# RGB_Display.net
KiCad netlist of a schematic drawn in Altium Designer
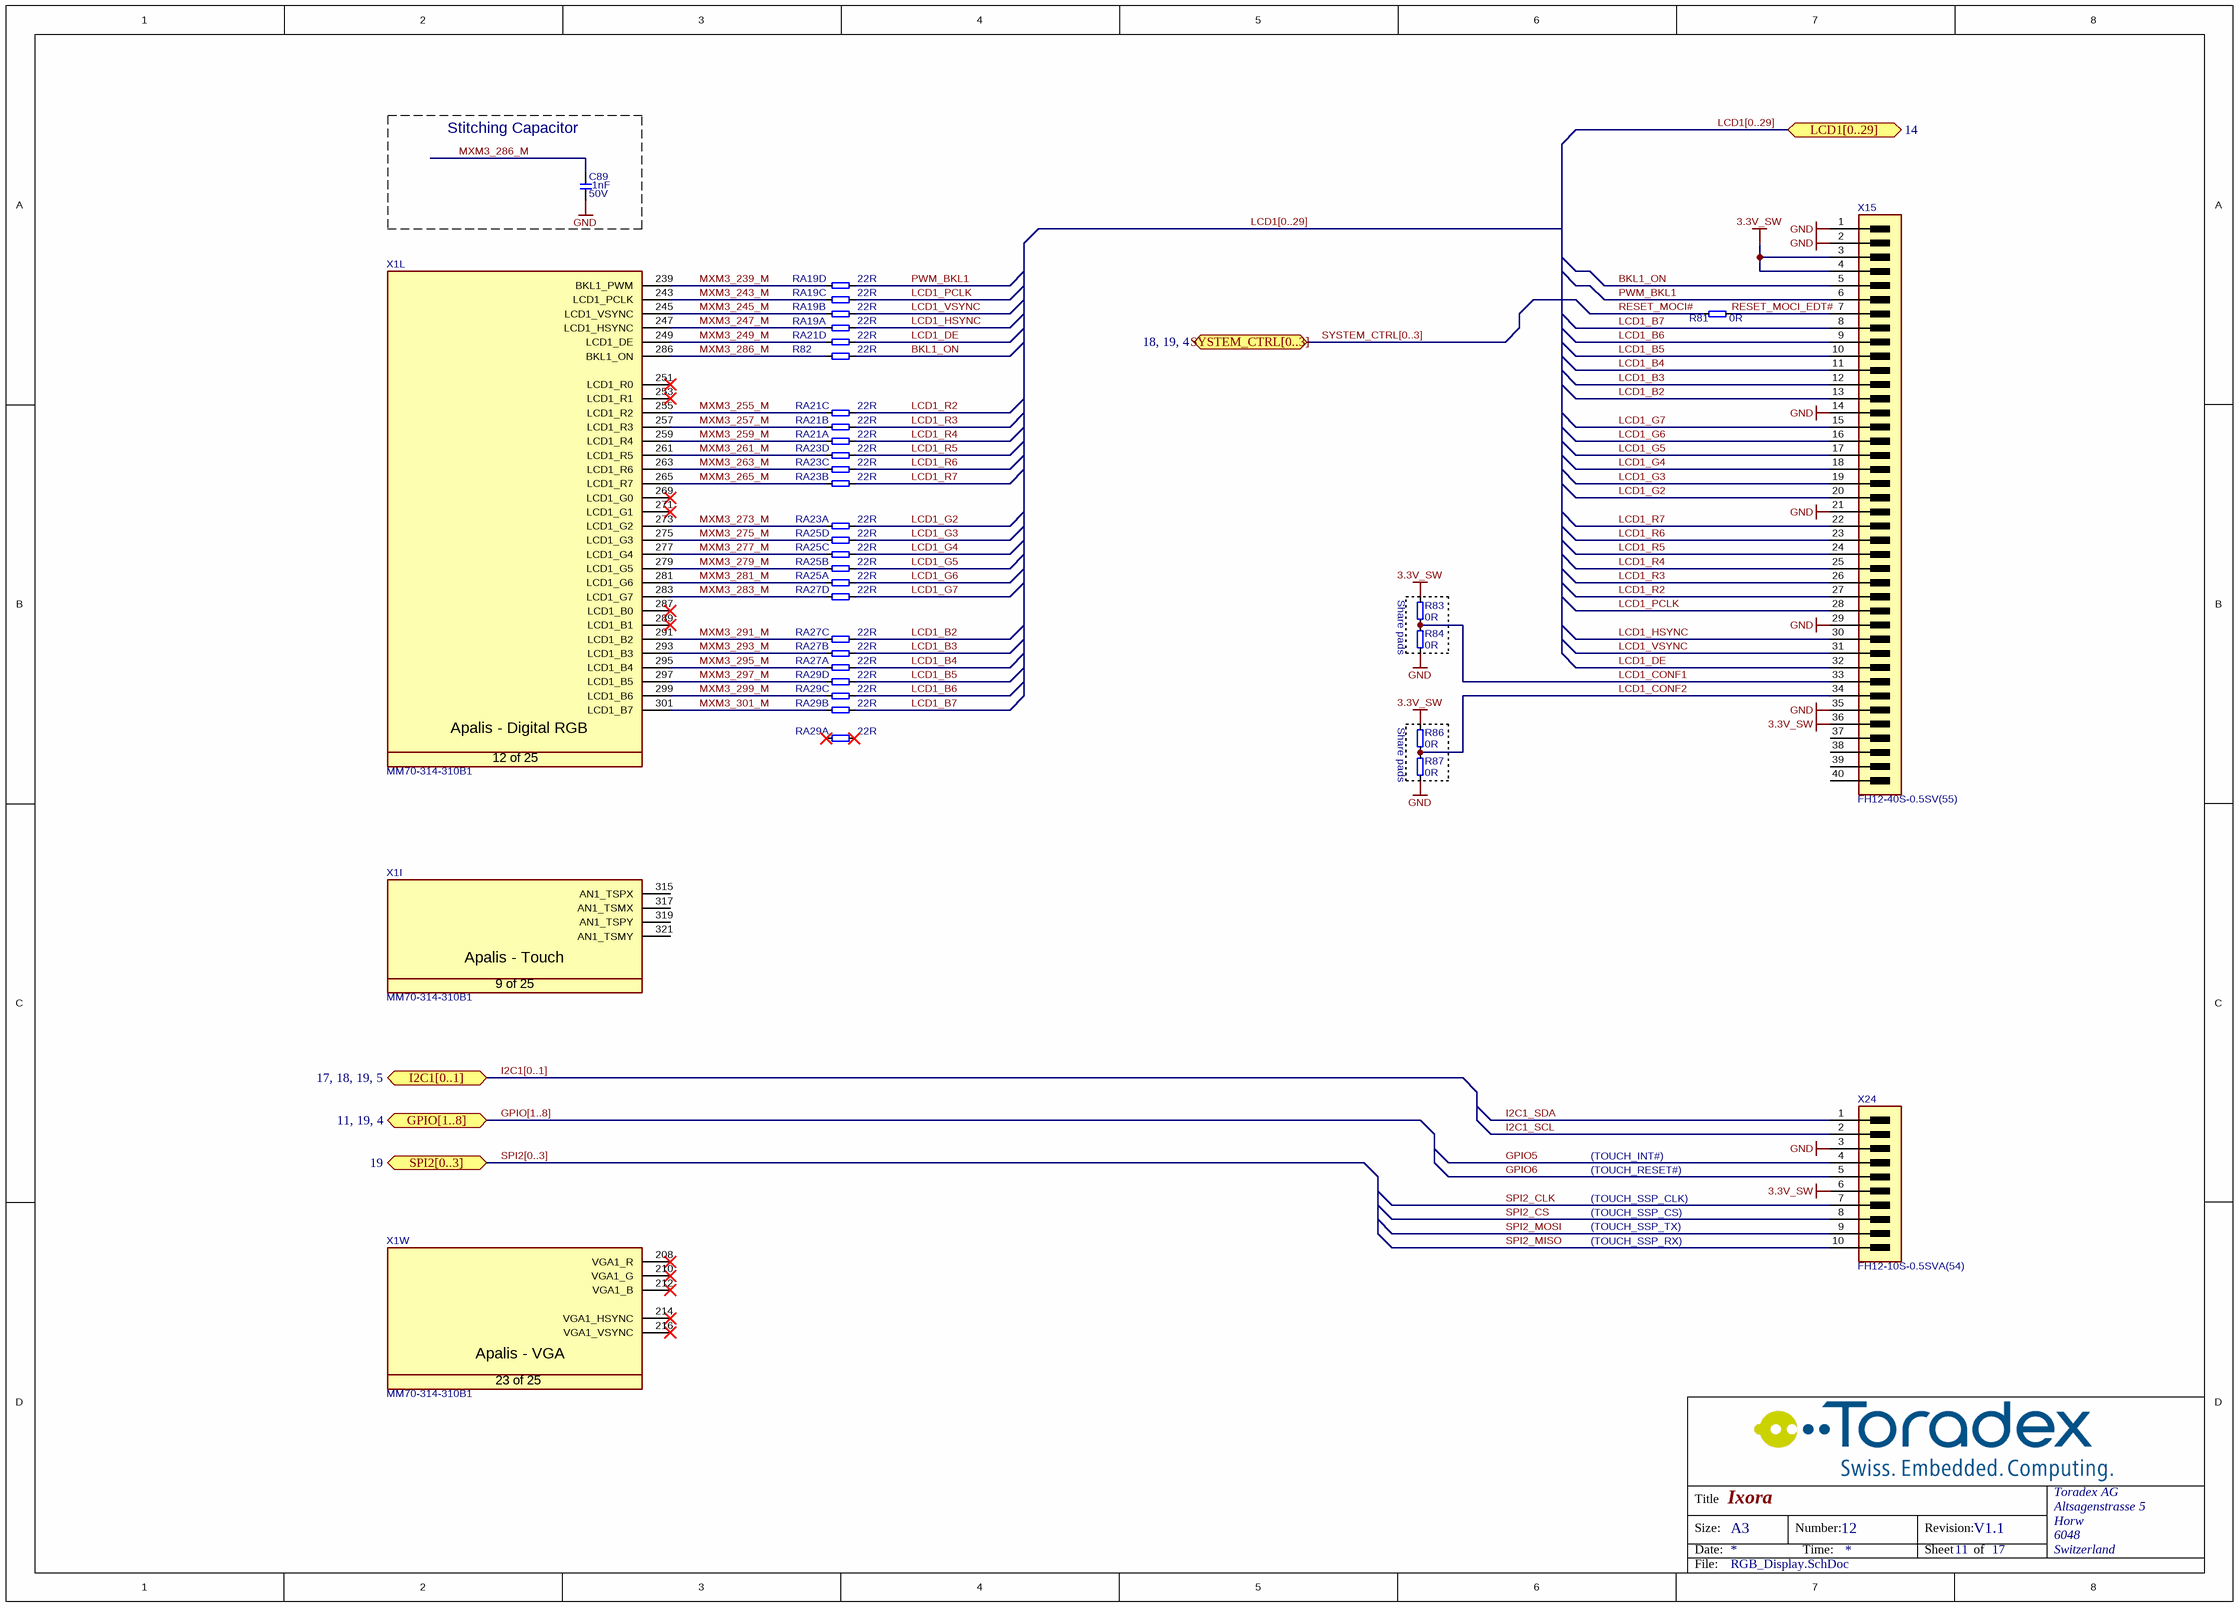
[diagram p0: RGB_Display.SchDoc]

(export (version "E")
  (design (tool "Eeschema 10.0.6"))
  (components
    (comp (ref "C89")
      (value "1nF")
      (footprint "CAPC1005X60N")
      (description "Capacitor Ceramic X7R 1nF 50V 10% 0402")
      (fields (field (name "TOLERANCE") "10%") (field (name "RATING") "50V"))
      (libsource (lib "Ixora") (part "C-X7R-1nF-50V-10%-0402"))
    )
    (comp (ref "R81")
      (value "0R")
      (footprint "RESC1005X40N")
      (description "Resistor 0 ohm 63mW 1% 0402")
      (fields (field (name "TOLERANCE") "1%"))
      (libsource (lib "Ixora") (part "R-0R-63mW-1%-0402"))
    )
    (comp (ref "R82")
      (value "22R")
      (footprint "RESC1005X40N")
      (description "Resistor 22 ohm 63mW 5% 0402")
      (fields (field (name "TOLERANCE") "5%"))
      (libsource (lib "Ixora") (part "R-22R-63mW-5%-0402"))
    )
    (comp (ref "R83")
      (value "0R")
      (footprint "T_RESC0603X30N")
      (description "Resistor 0 ohm 63mW 1% 0603")
      (fields (field (name "TOLERANCE") "1%"))
      (libsource (lib "Ixora") (part "R-0R-63mW-1%-0603"))
    )
    (comp (ref "R84")
      (value "0R")
      (footprint "T_RESC0603X30N")
      (description "Resistor 0 ohm 63mW 1% 0603")
      (fields (field (name "TOLERANCE") "1%"))
      (libsource (lib "Ixora") (part "R-0R-63mW-1%-0603"))
    )
    (comp (ref "R86")
      (value "0R")
      (footprint "T_RESC0603X30N")
      (description "Resistor 0 ohm 63mW 1% 0603")
      (fields (field (name "TOLERANCE") "1%"))
      (libsource (lib "Ixora") (part "R-0R-63mW-1%-0603"))
    )
    (comp (ref "R87")
      (value "0R")
      (footprint "T_RESC0603X30N")
      (description "Resistor 0 ohm 63mW 1% 0603")
      (fields (field (name "TOLERANCE") "1%"))
      (libsource (lib "Ixora") (part "R-0R-63mW-1%-0603"))
    )
    (comp (ref "RA19")
      (value "22R")
      (footprint "T_Resistor_Array_X4")
      (description "Resistor Array 22 R 63mW 5% 1206")
      (fields (field (name "TOLERANCE") "5%"))
      (libsource (lib "Ixora") (part "RA-22R-63mW-5%-1206-div"))
    )
    (comp (ref "RA21")
      (value "22R")
      (footprint "T_Resistor_Array_X4")
      (description "Resistor Array 22 R 63mW 5% 1206")
      (fields (field (name "TOLERANCE") "5%"))
      (libsource (lib "Ixora") (part "RA-22R-63mW-5%-1206-div"))
    )
    (comp (ref "RA23")
      (value "22R")
      (footprint "T_Resistor_Array_X4")
      (description "Resistor Array 22 R 63mW 5% 1206")
      (fields (field (name "TOLERANCE") "5%"))
      (libsource (lib "Ixora") (part "RA-22R-63mW-5%-1206-div"))
    )
    (comp (ref "RA25")
      (value "22R")
      (footprint "T_Resistor_Array_X4")
      (description "Resistor Array 22 R 63mW 5% 1206")
      (fields (field (name "TOLERANCE") "5%"))
      (libsource (lib "Ixora") (part "RA-22R-63mW-5%-1206-div"))
    )
    (comp (ref "RA27")
      (value "22R")
      (footprint "T_Resistor_Array_X4")
      (description "Resistor Array 22 R 63mW 5% 1206")
      (fields (field (name "TOLERANCE") "5%"))
      (libsource (lib "Ixora") (part "RA-22R-63mW-5%-1206-div"))
    )
    (comp (ref "RA29")
      (value "22R")
      (footprint "T_Resistor_Array_X4")
      (description "Resistor Array 22 R 63mW 5% 1206")
      (fields (field (name "TOLERANCE") "5%"))
      (libsource (lib "Ixora") (part "RA-22R-63mW-5%-1206-div"))
    )
    (comp (ref "X1")
      (value "CON-JAE-MM70-314-310B1-314-0.5mm")
      (footprint "T_JAE_MM70-314-310B1")
      (description "MXM3 Connector")
      (fields (field (name "MANUFACTURER PART NO.") "MM70-314-310B1"))
      (libsource (lib "Ixora") (part "CON-JAE-MM70-314-310B1-314-0.5mm"))
    )
    (comp (ref "X15")
      (value "FH12-40S-0.5SV(55)")
      (footprint "T_Hirose_FH12-40S-0.5SV(55)")
      (description "0.50mm Pitch FFC/FPC Vertical RGB connector")
      (fields (field (name "MANUFACTURER PART NO.") "FH12-40S-0.5SV(55)"))
      (libsource (lib "Ixora") (part "CON-Hirose-FH12-40S-0.5SV(55)-0.5mm"))
    )
    (comp (ref "X24")
      (value "FH12-10S-0.5SVA(54)")
      (footprint "T_Hirose_FH12-10S-0.5SVA(54)")
      (description "FFC/FPC, 1 Sided Contact, 0.50mm Pitch, 10 pins")
      (fields (field (name "MANUFACTURER PART NO.") "FH12-10S-0.5SVA(54)"))
      (libsource (lib "Ixora") (part "CON-Hirose-FH12-10S-0.5SVA(54)-0.5mm"))
    )
  )
  (nets
    (net (code "47") (name "/BKL1_ON") (class "Default")
      (node (ref "R82") (pin "2") (pinfunction "2_2") (pintype "passive"))
      (node (ref "X15") (pin "5") (pinfunction "PWCTRL_5") (pintype "passive"))
    )
    (net (code "48") (name "/GPIO5") (class "Default")
      (node (ref "X24") (pin "4") (pinfunction "GND_4") (pintype "passive"))
    )
    (net (code "49") (name "/GPIO6") (class "Default")
      (node (ref "X24") (pin "5") (pinfunction "TMDS_DATA0_P_5") (pintype "passive"))
    )
    (net (code "52") (name "/I2C1_SCL") (class "Default")
      (node (ref "X24") (pin "2") (pinfunction "TMDS_CLK_P_2") (pintype "passive"))
    )
    (net (code "53") (name "/I2C1_SDA") (class "Default")
      (node (ref "X24") (pin "1") (pinfunction "GND_1") (pintype "passive"))
    )
    (net (code "55") (name "/LCD1_B2") (class "Default")
      (node (ref "RA27") (pin "7") (pinfunction "7_7") (pintype "passive"))
      (node (ref "X15") (pin "13") (pinfunction "B0_13") (pintype "passive"))
    )
    (net (code "56") (name "/LCD1_B3") (class "Default")
      (node (ref "RA27") (pin "6") (pinfunction "6_6") (pintype "passive"))
      (node (ref "X15") (pin "12") (pinfunction "B1_12") (pintype "passive"))
    )
    (net (code "57") (name "/LCD1_B4") (class "Default")
      (node (ref "RA27") (pin "5") (pinfunction "5_5") (pintype "passive"))
      (node (ref "X15") (pin "11") (pinfunction "B2_11") (pintype "passive"))
    )
    (net (code "58") (name "/LCD1_B5") (class "Default")
      (node (ref "RA29") (pin "8") (pinfunction "8_8") (pintype "passive"))
      (node (ref "X15") (pin "10") (pinfunction "B3_10") (pintype "passive"))
    )
    (net (code "59") (name "/LCD1_B6") (class "Default")
      (node (ref "RA29") (pin "7") (pinfunction "7_7") (pintype "passive"))
      (node (ref "X15") (pin "9") (pinfunction "B4_9") (pintype "passive"))
    )
    (net (code "60") (name "/LCD1_B7") (class "Default")
      (node (ref "RA29") (pin "6") (pinfunction "6_6") (pintype "passive"))
      (node (ref "X15") (pin "8") (pinfunction "B5_8") (pintype "passive"))
    )
    (net (code "61") (name "/LCD1_CONF1") (class "Default")
      (node (ref "R83") (pin "2") (pinfunction "2_2") (pintype "passive"))
      (node (ref "R84") (pin "1") (pinfunction "1_1") (pintype "passive"))
      (node (ref "X15") (pin "33") (pinfunction "NC_33") (pintype "passive"))
    )
    (net (code "62") (name "/LCD1_CONF2") (class "Default")
      (node (ref "R86") (pin "2") (pinfunction "2_2") (pintype "passive"))
      (node (ref "R87") (pin "2") (pinfunction "2_2") (pintype "passive"))
      (node (ref "X15") (pin "34") (pinfunction "SHUT_34") (pintype "passive"))
    )
    (net (code "63") (name "/LCD1_DE") (class "Default")
      (node (ref "RA21") (pin "8") (pinfunction "8_8") (pintype "passive"))
      (node (ref "X15") (pin "32") (pinfunction "ENB_32") (pintype "passive"))
    )
    (net (code "64") (name "/LCD1_G2") (class "Default")
      (node (ref "RA23") (pin "5") (pinfunction "5_5") (pintype "passive"))
      (node (ref "X15") (pin "20") (pinfunction "G0_20") (pintype "passive"))
    )
    (net (code "65") (name "/LCD1_G3") (class "Default")
      (node (ref "RA25") (pin "8") (pinfunction "8_8") (pintype "passive"))
      (node (ref "X15") (pin "19") (pinfunction "G1_19") (pintype "passive"))
    )
    (net (code "66") (name "/LCD1_G4") (class "Default")
      (node (ref "RA25") (pin "7") (pinfunction "7_7") (pintype "passive"))
      (node (ref "X15") (pin "18") (pinfunction "G2_18") (pintype "passive"))
    )
    (net (code "67") (name "/LCD1_G5") (class "Default")
      (node (ref "RA25") (pin "6") (pinfunction "6_6") (pintype "passive"))
      (node (ref "X15") (pin "17") (pinfunction "G3_17") (pintype "passive"))
    )
    (net (code "68") (name "/LCD1_G6") (class "Default")
      (node (ref "RA25") (pin "5") (pinfunction "5_5") (pintype "passive"))
      (node (ref "X15") (pin "16") (pinfunction "G4_16") (pintype "passive"))
    )
    (net (code "69") (name "/LCD1_G7") (class "Default")
      (node (ref "RA27") (pin "8") (pinfunction "8_8") (pintype "passive"))
      (node (ref "X15") (pin "15") (pinfunction "G5_15") (pintype "passive"))
    )
    (net (code "70") (name "/LCD1_HSYNC") (class "Default")
      (node (ref "RA19") (pin "5") (pinfunction "5_5") (pintype "passive"))
      (node (ref "X15") (pin "30") (pinfunction "HSYNC_30") (pintype "passive"))
    )
    (net (code "71") (name "/LCD1_PCLK") (class "Default")
      (node (ref "RA19") (pin "7") (pinfunction "7_7") (pintype "passive"))
      (node (ref "X15") (pin "28") (pinfunction "DCLK_28") (pintype "passive"))
    )
    (net (code "72") (name "/LCD1_R2") (class "Default")
      (node (ref "RA21") (pin "7") (pinfunction "7_7") (pintype "passive"))
      (node (ref "X15") (pin "27") (pinfunction "R0_27") (pintype "passive"))
    )
    (net (code "73") (name "/LCD1_R3") (class "Default")
      (node (ref "RA21") (pin "6") (pinfunction "6_6") (pintype "passive"))
      (node (ref "X15") (pin "26") (pinfunction "R1_26") (pintype "passive"))
    )
    (net (code "74") (name "/LCD1_R4") (class "Default")
      (node (ref "RA21") (pin "5") (pinfunction "5_5") (pintype "passive"))
      (node (ref "X15") (pin "25") (pinfunction "R2_25") (pintype "passive"))
    )
    (net (code "75") (name "/LCD1_R5") (class "Default")
      (node (ref "RA23") (pin "8") (pinfunction "8_8") (pintype "passive"))
      (node (ref "X15") (pin "24") (pinfunction "R3_24") (pintype "passive"))
    )
    (net (code "76") (name "/LCD1_R6") (class "Default")
      (node (ref "RA23") (pin "7") (pinfunction "7_7") (pintype "passive"))
      (node (ref "X15") (pin "23") (pinfunction "R4_23") (pintype "passive"))
    )
    (net (code "77") (name "/LCD1_R7") (class "Default")
      (node (ref "RA23") (pin "6") (pinfunction "6_6") (pintype "passive"))
      (node (ref "X15") (pin "22") (pinfunction "R5_22") (pintype "passive"))
    )
    (net (code "78") (name "/LCD1_VSYNC") (class "Default")
      (node (ref "RA19") (pin "6") (pinfunction "6_6") (pintype "passive"))
      (node (ref "X15") (pin "31") (pinfunction "VSYNC_31") (pintype "passive"))
    )
    (net (code "79") (name "/MXM3_239_M") (class "Default")
      (node (ref "RA19") (pin "4") (pinfunction "4_4") (pintype "passive"))
      (node (ref "X1") (pin "239") (pinfunction "BKL1_PWM_239") (pintype "passive"))
    )
    (net (code "80") (name "/MXM3_243_M") (class "Default")
      (node (ref "RA19") (pin "3") (pinfunction "3_3") (pintype "passive"))
      (node (ref "X1") (pin "243") (pinfunction "LCD1_PCLK_243") (pintype "passive"))
    )
    (net (code "81") (name "/MXM3_245_M") (class "Default")
      (node (ref "RA19") (pin "2") (pinfunction "2_2") (pintype "passive"))
      (node (ref "X1") (pin "245") (pinfunction "LCD1_VSYNC_245") (pintype "passive"))
    )
    (net (code "82") (name "/MXM3_247_M") (class "Default")
      (node (ref "RA19") (pin "1") (pinfunction "1_1") (pintype "passive"))
      (node (ref "X1") (pin "247") (pinfunction "LCD1_HSYNC_247") (pintype "passive"))
    )
    (net (code "83") (name "/MXM3_249_M") (class "Default")
      (node (ref "RA21") (pin "4") (pinfunction "4_4") (pintype "passive"))
      (node (ref "X1") (pin "249") (pinfunction "LCD1_DE_249") (pintype "passive"))
    )
    (net (code "84") (name "/MXM3_255_M") (class "Default")
      (node (ref "RA21") (pin "3") (pinfunction "3_3") (pintype "passive"))
      (node (ref "X1") (pin "255") (pinfunction "LCD1_R2_255") (pintype "passive"))
    )
    (net (code "85") (name "/MXM3_257_M") (class "Default")
      (node (ref "RA21") (pin "2") (pinfunction "2_2") (pintype "passive"))
      (node (ref "X1") (pin "257") (pinfunction "LCD1_R3_257") (pintype "passive"))
    )
    (net (code "86") (name "/MXM3_259_M") (class "Default")
      (node (ref "RA21") (pin "1") (pinfunction "1_1") (pintype "passive"))
      (node (ref "X1") (pin "259") (pinfunction "LCD1_R4_259") (pintype "passive"))
    )
    (net (code "87") (name "/MXM3_261_M") (class "Default")
      (node (ref "RA23") (pin "4") (pinfunction "4_4") (pintype "passive"))
      (node (ref "X1") (pin "261") (pinfunction "LCD1_R5_261") (pintype "passive"))
    )
    (net (code "88") (name "/MXM3_263_M") (class "Default")
      (node (ref "RA23") (pin "3") (pinfunction "3_3") (pintype "passive"))
      (node (ref "X1") (pin "263") (pinfunction "LCD1_R6_263") (pintype "passive"))
    )
    (net (code "89") (name "/MXM3_265_M") (class "Default")
      (node (ref "RA23") (pin "2") (pinfunction "2_2") (pintype "passive"))
      (node (ref "X1") (pin "265") (pinfunction "LCD1_R7_265") (pintype "passive"))
    )
    (net (code "90") (name "/MXM3_273_M") (class "Default")
      (node (ref "RA23") (pin "1") (pinfunction "1_1") (pintype "passive"))
      (node (ref "X1") (pin "273") (pinfunction "LCD1_G2_273") (pintype "passive"))
    )
    (net (code "91") (name "/MXM3_275_M") (class "Default")
      (node (ref "RA25") (pin "4") (pinfunction "4_4") (pintype "passive"))
      (node (ref "X1") (pin "275") (pinfunction "LCD1_G3_275") (pintype "passive"))
    )
    (net (code "92") (name "/MXM3_277_M") (class "Default")
      (node (ref "RA25") (pin "3") (pinfunction "3_3") (pintype "passive"))
      (node (ref "X1") (pin "277") (pinfunction "LCD1_G4_277") (pintype "passive"))
    )
    (net (code "93") (name "/MXM3_279_M") (class "Default")
      (node (ref "RA25") (pin "2") (pinfunction "2_2") (pintype "passive"))
      (node (ref "X1") (pin "279") (pinfunction "LCD1_G5_279") (pintype "passive"))
    )
    (net (code "94") (name "/MXM3_281_M") (class "Default")
      (node (ref "RA25") (pin "1") (pinfunction "1_1") (pintype "passive"))
      (node (ref "X1") (pin "281") (pinfunction "LCD1_G6_281") (pintype "passive"))
    )
    (net (code "95") (name "/MXM3_283_M") (class "Default")
      (node (ref "RA27") (pin "4") (pinfunction "4_4") (pintype "passive"))
      (node (ref "X1") (pin "283") (pinfunction "LCD1_G7_283") (pintype "passive"))
    )
    (net (code "96") (name "/MXM3_286_M") (class "Default")
      (node (ref "C89") (pin "2") (pinfunction "2_2") (pintype "passive"))
      (node (ref "R82") (pin "1") (pinfunction "1_1") (pintype "passive"))
      (node (ref "X1") (pin "286") (pinfunction "BKL1_ON_286") (pintype "passive"))
    )
    (net (code "97") (name "/MXM3_291_M") (class "Default")
      (node (ref "RA27") (pin "3") (pinfunction "3_3") (pintype "passive"))
      (node (ref "X1") (pin "291") (pinfunction "LCD1_B2_291") (pintype "passive"))
    )
    (net (code "98") (name "/MXM3_293_M") (class "Default")
      (node (ref "RA27") (pin "2") (pinfunction "2_2") (pintype "passive"))
      (node (ref "X1") (pin "293") (pinfunction "LCD1_B3_293") (pintype "passive"))
    )
    (net (code "99") (name "/MXM3_295_M") (class "Default")
      (node (ref "RA27") (pin "1") (pinfunction "1_1") (pintype "passive"))
      (node (ref "X1") (pin "295") (pinfunction "LCD1_B4_295") (pintype "passive"))
    )
    (net (code "100") (name "/MXM3_297_M") (class "Default")
      (node (ref "RA29") (pin "4") (pinfunction "4_4") (pintype "passive"))
      (node (ref "X1") (pin "297") (pinfunction "LCD1_B5_297") (pintype "passive"))
    )
    (net (code "101") (name "/MXM3_299_M") (class "Default")
      (node (ref "RA29") (pin "3") (pinfunction "3_3") (pintype "passive"))
      (node (ref "X1") (pin "299") (pinfunction "LCD1_B6_299") (pintype "passive"))
    )
    (net (code "102") (name "/MXM3_301_M") (class "Default")
      (node (ref "RA29") (pin "2") (pinfunction "2_2") (pintype "passive"))
      (node (ref "X1") (pin "301") (pinfunction "LCD1_B7_301") (pintype "passive"))
    )
    (net (code "103") (name "/PWM_BKL1") (class "Default")
      (node (ref "RA19") (pin "8") (pinfunction "8_8") (pintype "passive"))
      (node (ref "X15") (pin "6") (pinfunction "LEDCTRL_6") (pintype "passive"))
    )
    (net (code "104") (name "/RESET_MOCI#") (class "Default")
      (node (ref "R81") (pin "1") (pinfunction "1_1") (pintype "passive"))
    )
    (net (code "105") (name "/RESET_MOCI_EDT#") (class "Default")
      (node (ref "R81") (pin "2") (pinfunction "2_2") (pintype "passive"))
      (node (ref "X15") (pin "7") (pinfunction "RESET#_7") (pintype "passive"))
    )
    (net (code "107") (name "/SPI2_CLK") (class "Default")
      (node (ref "X24") (pin "7") (pinfunction "GND_7") (pintype "passive"))
    )
    (net (code "108") (name "/SPI2_CS") (class "Default")
      (node (ref "X24") (pin "8") (pinfunction "TMDS_DATA1_P_8") (pintype "passive"))
    )
    (net (code "109") (name "/SPI2_MISO") (class "Default")
      (node (ref "X24") (pin "10") (pinfunction "GND_10") (pintype "passive"))
    )
    (net (code "110") (name "/SPI2_MOSI") (class "Default")
      (node (ref "X24") (pin "9") (pinfunction "TMDS_DATA1_N_9") (pintype "passive"))
    )
    (net (code "112") (name "3.3V_SW") (class "Default")
      (node (ref "R83") (pin "1") (pinfunction "1_1") (pintype "passive"))
      (node (ref "R86") (pin "1") (pinfunction "1_1") (pintype "passive"))
      (node (ref "X15") (pin "3") (pinfunction "VCC_3") (pintype "power_in"))
      (node (ref "X15") (pin "36") (pinfunction "VDD_36") (pintype "passive"))
      (node (ref "X15") (pin "4") (pinfunction "VCC_4") (pintype "power_in"))
      (node (ref "X24") (pin "6") (pinfunction "TMDS_DATA0_N_6") (pintype "passive"))
    )
    (net (code "113") (name "GND") (class "Default")
      (node (ref "C89") (pin "1") (pinfunction "1_1") (pintype "passive"))
      (node (ref "R84") (pin "2") (pinfunction "2_2") (pintype "passive"))
      (node (ref "R87") (pin "1") (pinfunction "1_1") (pintype "passive"))
      (node (ref "X15") (pin "1") (pinfunction "VSS_1") (pintype "power_in"))
      (node (ref "X15") (pin "14") (pinfunction "VSS_14") (pintype "passive"))
      (node (ref "X15") (pin "2") (pinfunction "VSS_2") (pintype "power_in"))
      (node (ref "X15") (pin "21") (pinfunction "VSS_21") (pintype "passive"))
      (node (ref "X15") (pin "29") (pinfunction "VSS_29") (pintype "passive"))
      (node (ref "X15") (pin "35") (pinfunction "VSS_35") (pintype "passive"))
      (node (ref "X24") (pin "3") (pinfunction "TMDS_CLK_N_3") (pintype "passive"))
    )
    (net (code "114") (name "unconnected-(RA29-Pad1)") (class "Default")
      (node (ref "RA29") (pin "1") (pinfunction "1_1") (pintype "passive+no_connect"))
    )
    (net (code "115") (name "unconnected-(RA29-Pad5)") (class "Default")
      (node (ref "RA29") (pin "5") (pinfunction "5_5") (pintype "passive+no_connect"))
    )
    (net (code "116") (name "unconnected-(X1I-AN1_TSMX-Pad317)") (class "Default")
      (node (ref "X1") (pin "317") (pinfunction "AN1_TSMX_317") (pintype "passive"))
    )
    (net (code "117") (name "unconnected-(X1I-AN1_TSMY-Pad321)") (class "Default")
      (node (ref "X1") (pin "321") (pinfunction "AN1_TSMY_321") (pintype "passive"))
    )
    (net (code "118") (name "unconnected-(X1I-AN1_TSPX-Pad315)") (class "Default")
      (node (ref "X1") (pin "315") (pinfunction "AN1_TSPX_315") (pintype "passive"))
    )
    (net (code "119") (name "unconnected-(X1I-AN1_TSPY-Pad319)") (class "Default")
      (node (ref "X1") (pin "319") (pinfunction "AN1_TSPY_319") (pintype "passive"))
    )
    (net (code "120") (name "unconnected-(X1L-LCD1_B0-Pad287)") (class "Default")
      (node (ref "X1") (pin "287") (pinfunction "LCD1_B0_287") (pintype "passive+no_connect"))
    )
    (net (code "121") (name "unconnected-(X1L-LCD1_B1-Pad289)") (class "Default")
      (node (ref "X1") (pin "289") (pinfunction "LCD1_B1_289") (pintype "passive+no_connect"))
    )
    (net (code "122") (name "unconnected-(X1L-LCD1_G0-Pad269)") (class "Default")
      (node (ref "X1") (pin "269") (pinfunction "LCD1_G0_269") (pintype "passive+no_connect"))
    )
    (net (code "123") (name "unconnected-(X1L-LCD1_G1-Pad271)") (class "Default")
      (node (ref "X1") (pin "271") (pinfunction "LCD1_G1_271") (pintype "passive+no_connect"))
    )
    (net (code "124") (name "unconnected-(X1L-LCD1_R0-Pad251)") (class "Default")
      (node (ref "X1") (pin "251") (pinfunction "LCD1_R0_251") (pintype "passive+no_connect"))
    )
    (net (code "125") (name "unconnected-(X1L-LCD1_R1-Pad253)") (class "Default")
      (node (ref "X1") (pin "253") (pinfunction "LCD1_R1_253") (pintype "passive+no_connect"))
    )
    (net (code "126") (name "unconnected-(X1W-VGA1_B-Pad212)") (class "Default")
      (node (ref "X1") (pin "212") (pinfunction "VGA1_B_212") (pintype "passive+no_connect"))
    )
    (net (code "127") (name "unconnected-(X1W-VGA1_G-Pad210)") (class "Default")
      (node (ref "X1") (pin "210") (pinfunction "VGA1_G_210") (pintype "passive+no_connect"))
    )
    (net (code "128") (name "unconnected-(X1W-VGA1_HSYNC-Pad214)") (class "Default")
      (node (ref "X1") (pin "214") (pinfunction "VGA1_HSYNC_214") (pintype "passive+no_connect"))
    )
    (net (code "129") (name "unconnected-(X1W-VGA1_R-Pad208)") (class "Default")
      (node (ref "X1") (pin "208") (pinfunction "VGA1_R_208") (pintype "passive+no_connect"))
    )
    (net (code "130") (name "unconnected-(X1W-VGA1_VSYNC-Pad216)") (class "Default")
      (node (ref "X1") (pin "216") (pinfunction "VGA1_VSYNC_216") (pintype "passive+no_connect"))
    )
    (net (code "131") (name "unconnected-(X15-XL-Pad40)") (class "Default")
      (node (ref "X15") (pin "40") (pinfunction "XL_40") (pintype "passive"))
    )
    (net (code "132") (name "unconnected-(X15-XR-Pad38)") (class "Default")
      (node (ref "X15") (pin "38") (pinfunction "XR_38") (pintype "passive"))
    )
    (net (code "133") (name "unconnected-(X15-YD-Pad39)") (class "Default")
      (node (ref "X15") (pin "39") (pinfunction "YD_39") (pintype "passive"))
    )
    (net (code "134") (name "unconnected-(X15-YU-Pad37)") (class "Default")
      (node (ref "X15") (pin "37") (pinfunction "YU_37") (pintype "passive"))
    )
  )
)
